# Main.net
KiCad netlist of a schematic drawn in Altium Designer
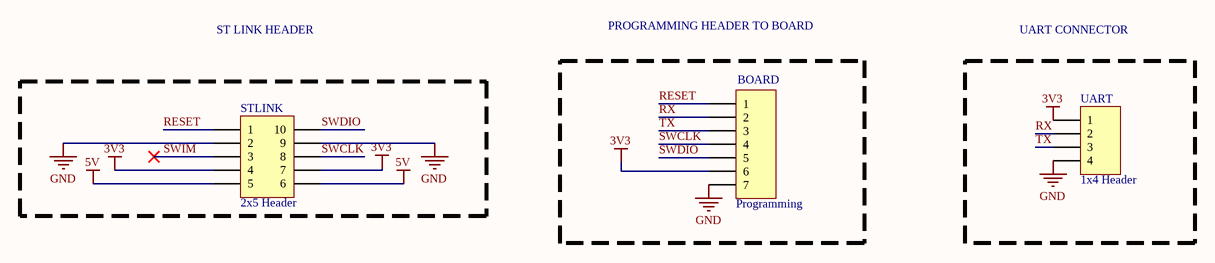
[diagram p0: Main.SchDoc]

(export (version "E")
  (design (tool "Eeschema 10.0.6"))
  (components
    (comp (ref "BOARD")
      (value "Programming")
      (footprint "HDR1X7")
      (description "1x7 Pin Header")
      (libsource (lib "GeneralConnectors") (part "1x7 Header"))
    )
    (comp (ref "STLINK")
      (value "2x5 Header")
      (footprint "HDR2x5")
      (description "2x5 Pin Header")
      (libsource (lib "GeneralConnectors") (part "2x5 Header"))
    )
    (comp (ref "UART")
      (value "1x4 Header")
      (footprint "HDR1X4")
      (description "1x4 Pin Header")
      (libsource (lib "GeneralConnectors") (part "1x4 Header"))
    )
  )
  (nets
    (net (code "1") (name "/RESET") (class "Default")
      (node (ref "BOARD") (pin "1") (pinfunction "1_1") (pintype "passive"))
      (node (ref "STLINK") (pin "1") (pinfunction "1_1") (pintype "passive"))
    )
    (net (code "2") (name "/RX") (class "Default")
      (node (ref "BOARD") (pin "2") (pinfunction "2_2") (pintype "passive"))
      (node (ref "UART") (pin "2") (pinfunction "2_2") (pintype "passive"))
    )
    (net (code "3") (name "/SWCLK") (class "Default")
      (node (ref "BOARD") (pin "4") (pinfunction "4_4") (pintype "passive"))
      (node (ref "STLINK") (pin "8") (pinfunction "8_8") (pintype "passive"))
    )
    (net (code "4") (name "/SWDIO") (class "Default")
      (node (ref "BOARD") (pin "5") (pinfunction "5_5") (pintype "passive"))
      (node (ref "STLINK") (pin "10") (pinfunction "10_10") (pintype "passive"))
    )
    (net (code "5") (name "/SWIM") (class "Default")
      (node (ref "STLINK") (pin "3") (pinfunction "3_3") (pintype "passive+no_connect"))
    )
    (net (code "6") (name "/TX") (class "Default")
      (node (ref "BOARD") (pin "3") (pinfunction "3_3") (pintype "passive"))
      (node (ref "UART") (pin "3") (pinfunction "3_3") (pintype "passive"))
    )
    (net (code "7") (name "3V3") (class "Default")
      (node (ref "BOARD") (pin "6") (pinfunction "6_6") (pintype "passive"))
      (node (ref "STLINK") (pin "4") (pinfunction "4_4") (pintype "passive"))
      (node (ref "STLINK") (pin "7") (pinfunction "7_7") (pintype "passive"))
      (node (ref "UART") (pin "1") (pinfunction "1_1") (pintype "passive"))
    )
    (net (code "8") (name "5V") (class "Default")
      (node (ref "STLINK") (pin "5") (pinfunction "5_5") (pintype "passive"))
      (node (ref "STLINK") (pin "6") (pinfunction "6_6") (pintype "passive"))
    )
    (net (code "9") (name "GND") (class "Default")
      (node (ref "BOARD") (pin "7") (pinfunction "7_7") (pintype "passive"))
      (node (ref "STLINK") (pin "2") (pinfunction "2_2") (pintype "passive"))
      (node (ref "STLINK") (pin "9") (pinfunction "9_9") (pintype "passive"))
      (node (ref "UART") (pin "4") (pinfunction "4_4") (pintype "passive"))
    )
  )
)
